# 12ziban.net
KiCad netlist of a schematic drawn in Altium Designer
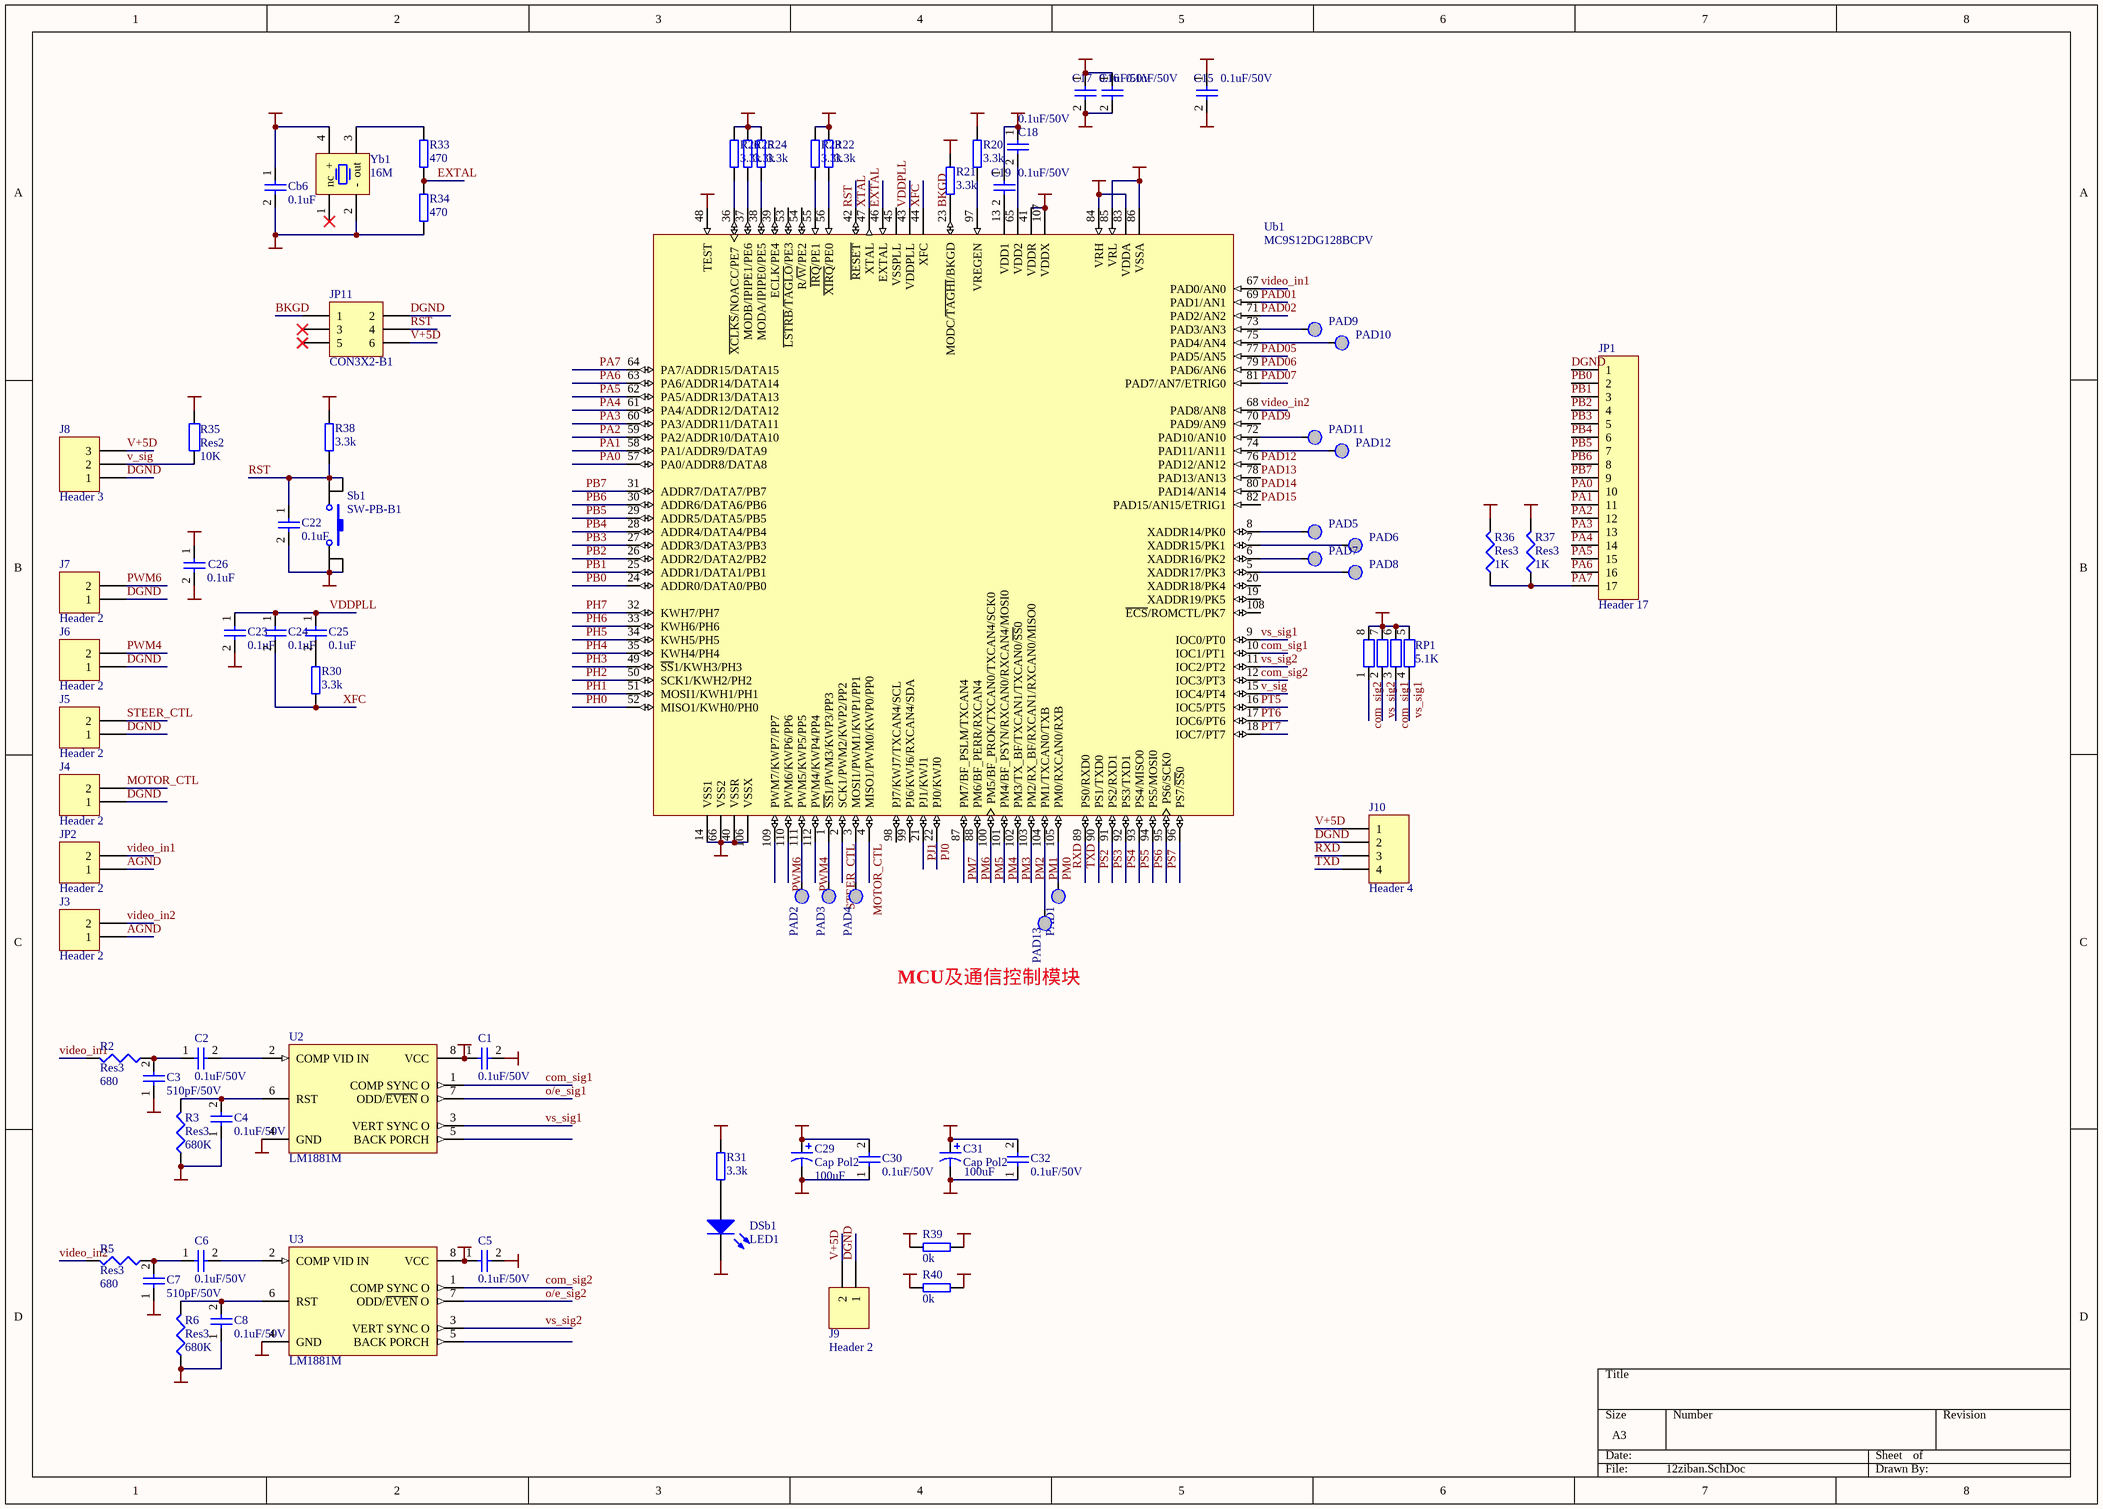
[diagram p0: 12ziban.SchDoc]

(export (version "E")
  (design (tool "Eeschema 10.0.6"))
  (components
    (comp (ref "C1")
      (value "0.1uF/50V")
      (footprint "CR2012-0805")
      (description "Capacitor")
      (fields
        (field (name "MANUFACTURER") "Generic Components")
        (field (name "Comment") "Cap")
        (field (name "PUBLISHER") "Altium Hobart Technology Centre")
      )
      (libsource (lib "YX002") (part "Cap"))
    )
    (comp (ref "C2")
      (value "0.1uF/50V")
      (footprint "CR2012-0805")
      (description "Capacitor")
      (fields
        (field (name "MANUFACTURER") "Generic Components")
        (field (name "Comment") "Cap")
        (field (name "PUBLISHER") "Altium Hobart Technology Centre")
      )
      (libsource (lib "YX002") (part "Cap"))
    )
    (comp (ref "C3")
      (value "510pF/50V")
      (footprint "CR2012-0805")
      (description "Capacitor")
      (fields
        (field (name "MANUFACTURER") "Generic Components")
        (field (name "Comment") "Cap")
        (field (name "PUBLISHER") "Altium Hobart Technology Centre")
      )
      (libsource (lib "YX002") (part "Cap"))
    )
    (comp (ref "C4")
      (value "0.1uF/50V")
      (footprint "CR2012-0805")
      (description "Capacitor")
      (fields
        (field (name "MANUFACTURER") "Generic Components")
        (field (name "Comment") "Cap")
        (field (name "PUBLISHER") "Altium Hobart Technology Centre")
      )
      (libsource (lib "YX002") (part "Cap"))
    )
    (comp (ref "C5")
      (value "0.1uF/50V")
      (footprint "CR2012-0805")
      (description "Capacitor")
      (fields
        (field (name "MANUFACTURER") "Generic Components")
        (field (name "Comment") "Cap")
        (field (name "PUBLISHER") "Altium Hobart Technology Centre")
      )
      (libsource (lib "YX002") (part "Cap"))
    )
    (comp (ref "C6")
      (value "0.1uF/50V")
      (footprint "CR2012-0805")
      (description "Capacitor")
      (fields
        (field (name "MANUFACTURER") "Generic Components")
        (field (name "Comment") "Cap")
        (field (name "PUBLISHER") "Altium Hobart Technology Centre")
      )
      (libsource (lib "YX002") (part "Cap"))
    )
    (comp (ref "C7")
      (value "510pF/50V")
      (footprint "CR2012-0805")
      (description "Capacitor")
      (fields
        (field (name "MANUFACTURER") "Generic Components")
        (field (name "Comment") "Cap")
        (field (name "PUBLISHER") "Altium Hobart Technology Centre")
      )
      (libsource (lib "YX002") (part "Cap"))
    )
    (comp (ref "C8")
      (value "0.1uF/50V")
      (footprint "CR2012-0805")
      (description "Capacitor")
      (fields
        (field (name "MANUFACTURER") "Generic Components")
        (field (name "Comment") "Cap")
        (field (name "PUBLISHER") "Altium Hobart Technology Centre")
      )
      (libsource (lib "YX002") (part "Cap"))
    )
    (comp (ref "C15")
      (value "0.1uF/50V")
      (footprint "CR2012-0805")
      (description "Capacitor")
      (fields
        (field (name "MANUFACTURER") "Generic Components")
        (field (name "Comment") "Cap")
        (field (name "PUBLISHER") "Altium Hobart Technology Centre")
      )
      (libsource (lib "YX002") (part "Cap"))
    )
    (comp (ref "C16")
      (value "0.1uF/50V")
      (footprint "CR2012-0805")
      (description "Capacitor")
      (fields
        (field (name "MANUFACTURER") "Generic Components")
        (field (name "Comment") "Cap")
        (field (name "PUBLISHER") "Altium Hobart Technology Centre")
      )
      (libsource (lib "YX002") (part "Cap"))
    )
    (comp (ref "C17")
      (value "0.1uF/50V")
      (footprint "CR2012-0805")
      (description "Capacitor")
      (fields
        (field (name "MANUFACTURER") "Generic Components")
        (field (name "Comment") "Cap")
        (field (name "PUBLISHER") "Altium Hobart Technology Centre")
      )
      (libsource (lib "YX002") (part "Cap"))
    )
    (comp (ref "C18")
      (value "0.1uF/50V")
      (footprint "CR2012-0805")
      (description "Capacitor")
      (fields
        (field (name "MANUFACTURER") "Generic Components")
        (field (name "Comment") "Cap")
        (field (name "PUBLISHER") "Altium Hobart Technology Centre")
      )
      (libsource (lib "YX002") (part "Cap"))
    )
    (comp (ref "C19")
      (value "0.1uF/50V")
      (footprint "CR2012-0805")
      (description "Capacitor")
      (fields
        (field (name "MANUFACTURER") "Generic Components")
        (field (name "Comment") "Cap")
        (field (name "PUBLISHER") "Altium Hobart Technology Centre")
      )
      (libsource (lib "YX002") (part "Cap"))
    )
    (comp (ref "C22")
      (value "0.1uF")
      (footprint "CR2012-0805")
      (description "Capacitor")
      (fields (field (name "Comment") "Cap") (field (name "PUBLISHER") "Altium Limited"))
      (libsource (lib "BFTC_MD") (part "Cap"))
    )
    (comp (ref "C23")
      (value "0.1uF")
      (footprint "CR2012-0805")
      (description "Capacitor")
      (fields
        (field (name "MANUFACTURER") "Generic Components")
        (field (name "Comment") "Cap")
        (field (name "PUBLISHER") "Altium Hobart Technology Centre")
      )
      (libsource (lib "*") (part "Cap"))
    )
    (comp (ref "C24")
      (value "0.1uF")
      (footprint "CR2012-0805")
      (description "Capacitor")
      (fields
        (field (name "MANUFACTURER") "Generic Components")
        (field (name "Comment") "Cap")
        (field (name "PUBLISHER") "Altium Hobart Technology Centre")
      )
      (libsource (lib "*") (part "Cap"))
    )
    (comp (ref "C25")
      (value "0.1uF")
      (footprint "CR2012-0805")
      (description "Capacitor")
      (fields
        (field (name "MANUFACTURER") "Generic Components")
        (field (name "Comment") "Cap")
        (field (name "PUBLISHER") "Altium Hobart Technology Centre")
      )
      (libsource (lib "*") (part "Cap"))
    )
    (comp (ref "C26")
      (value "0.1uF")
      (footprint "CR2012-0805")
      (description "Capacitor")
      (fields (field (name "Comment") "Cap") (field (name "PUBLISHER") "Altium Limited"))
      (libsource (lib "BFTC_MD") (part "Cap"))
    )
    (comp (ref "C29")
      (value "Cap Pol2")
      (footprint "CR6332-2512")
      (description "Polarized Capacitor (Axial)")
      (fields (field (name "ALTIUM_VALUE") "100uF") (field (name "PUBLISHER") "Altium Limited"))
      (libsource (lib "Miscellaneous Devices") (part "Cap Pol2"))
    )
    (comp (ref "C30")
      (value "0.1uF/50V")
      (footprint "CR2012-0805")
      (description "Capacitor")
      (fields
        (field (name "MANUFACTURER") "Generic Components")
        (field (name "Comment") "Cap")
        (field (name "PUBLISHER") "Altium Hobart Technology Centre")
      )
      (libsource (lib "YX002") (part "Cap"))
    )
    (comp (ref "C31")
      (value "Cap Pol2")
      (footprint "C3216-1206-TA-YX1")
      (description "Polarized Capacitor (Axial)")
      (fields (field (name "ALTIUM_VALUE") "100uF") (field (name "PUBLISHER") "Altium Limited"))
      (libsource (lib "Miscellaneous Devices") (part "Cap Pol2"))
    )
    (comp (ref "C32")
      (value "0.1uF/50V")
      (footprint "CR2012-0805")
      (description "Capacitor")
      (fields
        (field (name "MANUFACTURER") "Generic Components")
        (field (name "Comment") "Cap")
        (field (name "PUBLISHER") "Altium Hobart Technology Centre")
      )
      (libsource (lib "YX002") (part "Cap"))
    )
    (comp (ref "Cb6")
      (value "0.1uF")
      (footprint "CR2012-0805")
      (description "Capacitor")
      (fields
        (field (name "MANUFACTURER") "Generic Components")
        (field (name "Comment") "Cap")
        (field (name "PUBLISHER") "Altium Hobart Technology Centre")
      )
      (libsource (lib "*") (part "Cap"))
    )
    (comp (ref "DSb1")
      (value "LED1")
      (footprint "CR2012-0805")
      (description "Typical RED GaAs LED")
      (fields (field (name "PUBLISHER") "Altium Limited"))
      (libsource (lib "Miscellaneous Devices") (part "LED1"))
    )
    (comp (ref "J3")
      (value "Header 2")
      (footprint "HDR1X2")
      (description "Header, 2-Pin")
      (fields (field (name "PUBLISHER") "Altium Limited"))
      (libsource (lib "Miscellaneous Connectors") (part "Header 2"))
    )
    (comp (ref "J4")
      (value "Header 2")
      (footprint "HDR1X2")
      (description "Header, 2-Pin")
      (fields (field (name "PUBLISHER") "Altium Limited"))
      (libsource (lib "Miscellaneous Connectors") (part "Header 2"))
    )
    (comp (ref "J5")
      (value "Header 2")
      (footprint "HDR1X2")
      (description "Header, 2-Pin")
      (fields (field (name "PUBLISHER") "Altium Limited"))
      (libsource (lib "Miscellaneous Connectors") (part "Header 2"))
    )
    (comp (ref "J6")
      (value "Header 2")
      (footprint "HDR1X2")
      (description "Header, 2-Pin")
      (fields (field (name "PUBLISHER") "Altium Limited"))
      (libsource (lib "Miscellaneous Connectors") (part "Header 2"))
    )
    (comp (ref "J7")
      (value "Header 2")
      (footprint "HDR1X2")
      (description "Header, 2-Pin")
      (fields (field (name "PUBLISHER") "Altium Limited"))
      (libsource (lib "Miscellaneous Connectors") (part "Header 2"))
    )
    (comp (ref "J8")
      (value "Header 3")
      (footprint "HDR1X3")
      (description "Header, 3-Pin")
      (fields (field (name "PUBLISHER") "Altium Limited"))
      (libsource (lib "Miscellaneous Connectors") (part "Header 3"))
    )
    (comp (ref "J9")
      (value "Header 2")
      (footprint "HDR1X2")
      (description "Header, 2-Pin")
      (fields (field (name "PUBLISHER") "Altium Limited"))
      (libsource (lib "") (part "Header 2_1"))
    )
    (comp (ref "J10")
      (value "Header 4")
      (footprint "HDR1X4")
      (description "Header, 4-Pin")
      (fields (field (name "PUBLISHER") "Altium Limited"))
      (libsource (lib "Miscellaneous Connectors") (part "Header 4"))
    )
    (comp (ref "JP1")
      (value "Header 17")
      (footprint "Ts1x17")
      (description "Header, 17-Pin")
      (fields (field (name "PUBLISHER") "Altium Limited"))
      (libsource (lib "Miscellaneous Connectors") (part "Header 17"))
    )
    (comp (ref "JP2")
      (value "Header 2")
      (footprint "HDR1X2")
      (description "Header, 2-Pin")
      (fields (field (name "PUBLISHER") "Altium Limited"))
      (libsource (lib "Miscellaneous Connectors") (part "Header 2"))
    )
    (comp (ref "JP11")
      (value "CON3X2-B1")
      (footprint "HDR2X3")
      (description "Header, 6-Pin, Dual row")
      (fields (field (name "MANUFACTURER") "Generic Components"))
      (libsource (lib "BFTC_MC") (part "CON3X2-B1"))
    )
    (comp (ref "PAD1")
      (value "PAD-YX1")
      (footprint "PAD-TEST-YX1")
      (description "Electrical Bell")
      (fields (field (name "MANUFACTURER") "Generic Components"))
      (libsource (lib "ECU") (part "PAD-YX1"))
    )
    (comp (ref "PAD2")
      (value "PAD-YX1")
      (footprint "PAD-TEST-YX1")
      (description "Electrical Bell")
      (fields (field (name "MANUFACTURER") "Generic Components"))
      (libsource (lib "ECU") (part "PAD-YX1"))
    )
    (comp (ref "PAD3")
      (value "PAD-YX1")
      (footprint "PAD-TEST-YX1")
      (description "Electrical Bell")
      (fields (field (name "MANUFACTURER") "Generic Components"))
      (libsource (lib "ECU") (part "PAD-YX1"))
    )
    (comp (ref "PAD4")
      (value "PAD-YX1")
      (footprint "PAD-TEST-YX1")
      (description "Electrical Bell")
      (fields (field (name "MANUFACTURER") "Generic Components"))
      (libsource (lib "ECU") (part "PAD-YX1"))
    )
    (comp (ref "PAD5")
      (value "PAD-YX1")
      (footprint "PAD-TEST-YX1")
      (description "Electrical Bell")
      (fields (field (name "MANUFACTURER") "Generic Components"))
      (libsource (lib "ECU") (part "PAD-YX1"))
    )
    (comp (ref "PAD6")
      (value "PAD-YX1")
      (footprint "PAD-TEST-YX1")
      (description "Electrical Bell")
      (fields (field (name "MANUFACTURER") "Generic Components"))
      (libsource (lib "ECU") (part "PAD-YX1"))
    )
    (comp (ref "PAD7")
      (value "PAD-YX1")
      (footprint "PAD-TEST-YX1")
      (description "Electrical Bell")
      (fields (field (name "MANUFACTURER") "Generic Components"))
      (libsource (lib "ECU") (part "PAD-YX1"))
    )
    (comp (ref "PAD8")
      (value "PAD-YX1")
      (footprint "PAD-TEST-YX1")
      (description "Electrical Bell")
      (fields (field (name "MANUFACTURER") "Generic Components"))
      (libsource (lib "ECU") (part "PAD-YX1"))
    )
    (comp (ref "PAD9")
      (value "PAD-YX1")
      (footprint "PAD-TEST-YX1")
      (description "Electrical Bell")
      (fields (field (name "MANUFACTURER") "Generic Components"))
      (libsource (lib "ECU") (part "PAD-YX1"))
    )
    (comp (ref "PAD10")
      (value "PAD-YX1")
      (footprint "PAD-TEST-YX1")
      (description "Electrical Bell")
      (fields (field (name "MANUFACTURER") "Generic Components"))
      (libsource (lib "ECU") (part "PAD-YX1"))
    )
    (comp (ref "PAD11")
      (value "PAD-YX1")
      (footprint "PAD-TEST-YX1")
      (description "Electrical Bell")
      (fields (field (name "MANUFACTURER") "Generic Components"))
      (libsource (lib "ECU") (part "PAD-YX1"))
    )
    (comp (ref "PAD12")
      (value "PAD-YX1")
      (footprint "PAD-TEST-YX1")
      (description "Electrical Bell")
      (fields (field (name "MANUFACTURER") "Generic Components"))
      (libsource (lib "ECU") (part "PAD-YX1"))
    )
    (comp (ref "PAD13")
      (value "PAD-YX1")
      (footprint "PAD-TEST-YX1")
      (description "Electrical Bell")
      (fields (field (name "MANUFACTURER") "Generic Components"))
      (libsource (lib "ECU") (part "PAD-YX1"))
    )
    (comp (ref "R2")
      (value "Res3")
      (footprint "CR2012-0805")
      (description "Resistor")
      (fields (field (name "ALTIUM_VALUE") "680") (field (name "PUBLISHER") "Altium Limited"))
      (libsource (lib "Miscellaneous Devices") (part "Res3"))
    )
    (comp (ref "R3")
      (value "Res3")
      (footprint "CR2012-0805")
      (description "Resistor")
      (fields (field (name "ALTIUM_VALUE") "680K") (field (name "PUBLISHER") "Altium Limited"))
      (libsource (lib "Miscellaneous Devices") (part "Res3"))
    )
    (comp (ref "R5")
      (value "Res3")
      (footprint "CR2012-0805")
      (description "Resistor")
      (fields (field (name "ALTIUM_VALUE") "680") (field (name "PUBLISHER") "Altium Limited"))
      (libsource (lib "Miscellaneous Devices") (part "Res3"))
    )
    (comp (ref "R6")
      (value "Res3")
      (footprint "CR2012-0805")
      (description "Resistor")
      (fields (field (name "ALTIUM_VALUE") "680K") (field (name "PUBLISHER") "Altium Limited"))
      (libsource (lib "Miscellaneous Devices") (part "Res3"))
    )
    (comp (ref "R20") (value "3.3k") (footprint "CR2012-0805") (libsource (lib "*") (part "RES2")))
    (comp (ref "R21") (value "3.3k") (footprint "CR2012-0805") (libsource (lib "*") (part "RES2")))
    (comp (ref "R22") (value "3.3k") (footprint "CR2012-0805") (libsource (lib "*") (part "RES2")))
    (comp (ref "R23") (value "3.3k") (footprint "CR2012-0805") (libsource (lib "*") (part "RES2")))
    (comp (ref "R24") (value "3.3k") (footprint "CR2012-0805") (libsource (lib "*") (part "RES2")))
    (comp (ref "R25") (value "3.3k") (footprint "CR2012-0805") (libsource (lib "*") (part "RES2")))
    (comp (ref "R26") (value "3.3k") (footprint "CR2012-0805") (libsource (lib "*") (part "RES2")))
    (comp (ref "R30") (value "3.3k") (footprint "CR2012-0805") (libsource (lib "*") (part "RES2")))
    (comp (ref "R31") (value "3.3k") (footprint "CR2012-0805") (libsource (lib "*") (part "RES2")))
    (comp (ref "R33") (value "470") (footprint "CR2012-0805") (libsource (lib "*") (part "RES2")))
    (comp (ref "R34") (value "470") (footprint "CR2012-0805") (libsource (lib "*") (part "RES2")))
    (comp (ref "R35")
      (value "Res2")
      (footprint "CR2012-0805")
      (description "Resistor")
      (fields (field (name "ALTIUM_VALUE") "10K") (field (name "PUBLISHER") "Altium Limited"))
      (libsource (lib "Miscellaneous Devices") (part "Res2"))
    )
    (comp (ref "R36")
      (value "Res3")
      (footprint "CR2012-0805")
      (description "Resistor")
      (fields (field (name "ALTIUM_VALUE") "1K") (field (name "PUBLISHER") "Altium Limited"))
      (libsource (lib "Miscellaneous Devices") (part "Res3"))
    )
    (comp (ref "R37")
      (value "Res3")
      (footprint "CR2012-0805")
      (description "Resistor")
      (fields (field (name "ALTIUM_VALUE") "1K") (field (name "PUBLISHER") "Altium Limited"))
      (libsource (lib "Miscellaneous Devices") (part "Res3"))
    )
    (comp (ref "R38") (value "3.3k") (footprint "CR2012-0805") (libsource (lib "*") (part "RES2")))
    (comp (ref "R39") (value "0k") (footprint "CR2012-0805") (libsource (lib "*") (part "RES2")))
    (comp (ref "R40") (value "0k") (footprint "CR2012-0805") (libsource (lib "*") (part "RES2")))
    (comp (ref "RP1")
      (value "5.1K")
      (footprint "RP4_YX1")
      (description "Resistor")
      (fields
        (field (name "MANUFACTURER") "Generic Components")
        (field (name "Comment") "RESP4_YX1")
        (field (name "PUBLISHER") "Altium Hobart Technology Centre")
      )
      (libsource (lib "YX002") (part "RESP4_YX1"))
    )
    (comp (ref "Sb1")
      (value "SW-PB-B1")
      (footprint "SW2-4-B1")
      (description "Switch")
      (fields (field (name "MANUFACTURER") "Generic Components"))
      (libsource (lib "BFTC_MD") (part "SW-PB-B1"))
    )
    (comp (ref "U2")
      (value "LM1881M")
      (footprint "SO-8")
      (description "Video Sync Separator")
      (fields (field (name "PUBLISHER") "Altium Limited"))
      (libsource (lib "NSC Video Sync Circuit") (part "LM1881M"))
    )
    (comp (ref "U3")
      (value "LM1881M")
      (footprint "SO-8")
      (description "Video Sync Separator")
      (fields (field (name "PUBLISHER") "Altium Limited"))
      (libsource (lib "NSC Video Sync Circuit") (part "LM1881M"))
    )
    (comp (ref "Ub1")
      (value "MC9S12DG128BCPV")
      (footprint "987-01")
      (description "16-Bit Microcontroller")
      (fields (field (name "PUBLISHER") "Altium Limited"))
      (libsource (lib "Motorola Microcontroller 16-Bit") (part "MC9S12DG128BCPV"))
    )
    (comp (ref "Yb1")
      (value "16M")
      (footprint "XYT")
      (description "Crystal Oscillator")
      (fields
        (field (name "MANUFACTURER") "Generic Components")
        (field (name "Comment") "XTAL")
        (field (name "PUBLISHER") "Altium Hobart Technology Centre")
      )
      (libsource (lib "*") (part "XTAL-YX2"))
    )
  )
  (nets
    (net (code "1") (name "/BKGD") (class "Default")
      (node (ref "JP11") (pin "1") (pinfunction "1_1") (pintype "passive"))
      (node (ref "R21") (pin "2") (pinfunction "2_2") (pintype "passive"))
      (node (ref "Ub1") (pin "23") (pinfunction "MODC/~{TAGHI}/BKGD_23") (pintype "bidirectional"))
    )
    (net (code "2") (name "/EXTAL") (class "Default")
      (node (ref "R33") (pin "2") (pinfunction "2_2") (pintype "passive"))
      (node (ref "R34") (pin "1") (pinfunction "1_1") (pintype "passive"))
      (node (ref "Ub1") (pin "46") (pinfunction "EXTAL_46") (pintype "input"))
    )
    (net (code "3") (name "/MOTOR_CTL") (class "Default")
      (node (ref "J4") (pin "2") (pinfunction "2_2") (pintype "passive"))
      (node (ref "Ub1") (pin "4") (pinfunction "MISO1/PWM0/KWP0/PP0_4") (pintype "bidirectional"))
    )
    (net (code "4") (name "/PA0") (class "Default")
      (node (ref "JP1") (pin "10") (pinfunction "10_10") (pintype "passive"))
      (node (ref "Ub1") (pin "57") (pinfunction "PA0/ADDR8/DATA8_57") (pintype "bidirectional"))
    )
    (net (code "5") (name "/PA1") (class "Default")
      (node (ref "JP1") (pin "11") (pinfunction "11_11") (pintype "passive"))
      (node (ref "Ub1") (pin "58") (pinfunction "PA1/ADDR9/DATA9_58") (pintype "bidirectional"))
    )
    (net (code "6") (name "/PA2") (class "Default")
      (node (ref "JP1") (pin "12") (pinfunction "12_12") (pintype "passive"))
      (node (ref "Ub1") (pin "59") (pinfunction "PA2/ADDR10/DATA10_59") (pintype "bidirectional"))
    )
    (net (code "7") (name "/PA3") (class "Default")
      (node (ref "JP1") (pin "13") (pinfunction "13_13") (pintype "passive"))
      (node (ref "Ub1") (pin "60") (pinfunction "PA3/ADDR11/DATA11_60") (pintype "bidirectional"))
    )
    (net (code "8") (name "/PA4") (class "Default")
      (node (ref "JP1") (pin "14") (pinfunction "14_14") (pintype "passive"))
      (node (ref "Ub1") (pin "61") (pinfunction "PA4/ADDR12/DATA12_61") (pintype "bidirectional"))
    )
    (net (code "9") (name "/PA5") (class "Default")
      (node (ref "JP1") (pin "15") (pinfunction "15_15") (pintype "passive"))
      (node (ref "Ub1") (pin "62") (pinfunction "PA5/ADDR13/DATA13_62") (pintype "bidirectional"))
    )
    (net (code "10") (name "/PA6") (class "Default")
      (node (ref "JP1") (pin "16") (pinfunction "16_16") (pintype "passive"))
      (node (ref "Ub1") (pin "63") (pinfunction "PA6/ADDR14/DATA14_63") (pintype "bidirectional"))
    )
    (net (code "11") (name "/PA7") (class "Default")
      (node (ref "JP1") (pin "17") (pinfunction "17_17") (pintype "passive"))
      (node (ref "R36") (pin "1") (pinfunction "1_1") (pintype "passive"))
      (node (ref "R37") (pin "1") (pinfunction "1_1") (pintype "passive"))
      (node (ref "Ub1") (pin "64") (pinfunction "PA7/ADDR15/DATA15_64") (pintype "bidirectional"))
    )
    (net (code "12") (name "/PAD01") (class "Default")
      (node (ref "Ub1") (pin "69") (pinfunction "PAD1/AN1_69") (pintype "input"))
    )
    (net (code "13") (name "/PAD02") (class "Default")
      (node (ref "Ub1") (pin "71") (pinfunction "PAD2/AN2_71") (pintype "input"))
    )
    (net (code "14") (name "/PAD05") (class "Default")
      (node (ref "Ub1") (pin "77") (pinfunction "PAD5/AN5_77") (pintype "input"))
    )
    (net (code "15") (name "/PAD06") (class "Default")
      (node (ref "Ub1") (pin "79") (pinfunction "PAD6/AN6_79") (pintype "input"))
    )
    (net (code "16") (name "/PAD07") (class "Default")
      (node (ref "Ub1") (pin "81") (pinfunction "PAD7/AN7/ETRIG0_81") (pintype "input"))
    )
    (net (code "17") (name "/PAD9") (class "Default")
      (node (ref "Ub1") (pin "70") (pinfunction "PAD9/AN9_70") (pintype "input"))
    )
    (net (code "18") (name "/PAD12") (class "Default")
      (node (ref "Ub1") (pin "76") (pinfunction "PAD12/AN12_76") (pintype "input"))
    )
    (net (code "19") (name "/PAD13") (class "Default")
      (node (ref "Ub1") (pin "78") (pinfunction "PAD13/AN13_78") (pintype "input"))
    )
    (net (code "20") (name "/PAD14") (class "Default")
      (node (ref "Ub1") (pin "80") (pinfunction "PAD14/AN14_80") (pintype "input"))
    )
    (net (code "21") (name "/PAD15") (class "Default")
      (node (ref "Ub1") (pin "82") (pinfunction "PAD15/AN15/ETRIG1_82") (pintype "input"))
    )
    (net (code "22") (name "/PB0") (class "Default")
      (node (ref "JP1") (pin "2") (pinfunction "2_2") (pintype "passive"))
      (node (ref "Ub1") (pin "24") (pinfunction "ADDR0/DATA0/PB0_24") (pintype "bidirectional"))
    )
    (net (code "23") (name "/PB1") (class "Default")
      (node (ref "JP1") (pin "3") (pinfunction "3_3") (pintype "passive"))
      (node (ref "Ub1") (pin "25") (pinfunction "ADDR1/DATA1/PB1_25") (pintype "bidirectional"))
    )
    (net (code "24") (name "/PB2") (class "Default")
      (node (ref "JP1") (pin "4") (pinfunction "4_4") (pintype "passive"))
      (node (ref "Ub1") (pin "26") (pinfunction "ADDR2/DATA2/PB2_26") (pintype "bidirectional"))
    )
    (net (code "25") (name "/PB3") (class "Default")
      (node (ref "JP1") (pin "5") (pinfunction "5_5") (pintype "passive"))
      (node (ref "Ub1") (pin "27") (pinfunction "ADDR3/DATA3/PB3_27") (pintype "bidirectional"))
    )
    (net (code "26") (name "/PB4") (class "Default")
      (node (ref "JP1") (pin "6") (pinfunction "6_6") (pintype "passive"))
      (node (ref "Ub1") (pin "28") (pinfunction "ADDR4/DATA4/PB4_28") (pintype "bidirectional"))
    )
    (net (code "27") (name "/PB5") (class "Default")
      (node (ref "JP1") (pin "7") (pinfunction "7_7") (pintype "passive"))
      (node (ref "Ub1") (pin "29") (pinfunction "ADDR5/DATA5/PB5_29") (pintype "bidirectional"))
    )
    (net (code "28") (name "/PB6") (class "Default")
      (node (ref "JP1") (pin "8") (pinfunction "8_8") (pintype "passive"))
      (node (ref "Ub1") (pin "30") (pinfunction "ADDR6/DATA6/PB6_30") (pintype "bidirectional"))
    )
    (net (code "29") (name "/PB7") (class "Default")
      (node (ref "JP1") (pin "9") (pinfunction "9_9") (pintype "passive"))
      (node (ref "Ub1") (pin "31") (pinfunction "ADDR7/DATA7/PB7_31") (pintype "bidirectional"))
    )
    (net (code "30") (name "/PH0") (class "Default")
      (node (ref "Ub1") (pin "52") (pinfunction "MISO1/KWH0/PH0_52") (pintype "bidirectional"))
    )
    (net (code "31") (name "/PH1") (class "Default")
      (node (ref "Ub1") (pin "51") (pinfunction "MOSI1/KWH1/PH1_51") (pintype "bidirectional"))
    )
    (net (code "32") (name "/PH2") (class "Default")
      (node (ref "Ub1") (pin "50") (pinfunction "SCK1/KWH2/PH2_50") (pintype "bidirectional"))
    )
    (net (code "33") (name "/PH3") (class "Default")
      (node (ref "Ub1") (pin "49") (pinfunction "~{SS}1/KWH3/PH3_49") (pintype "bidirectional"))
    )
    (net (code "34") (name "/PH4") (class "Default")
      (node (ref "Ub1") (pin "35") (pinfunction "KWH4/PH4_35") (pintype "bidirectional"))
    )
    (net (code "35") (name "/PH5") (class "Default")
      (node (ref "Ub1") (pin "34") (pinfunction "KWH5/PH5_34") (pintype "bidirectional"))
    )
    (net (code "36") (name "/PH6") (class "Default")
      (node (ref "Ub1") (pin "33") (pinfunction "KWH6/PH6_33") (pintype "bidirectional"))
    )
    (net (code "37") (name "/PH7") (class "Default")
      (node (ref "Ub1") (pin "32") (pinfunction "KWH7/PH7_32") (pintype "bidirectional"))
    )
    (net (code "38") (name "/PJ0") (class "Default")
      (node (ref "Ub1") (pin "22") (pinfunction "PJ0/KWJ0_22") (pintype "bidirectional"))
    )
    (net (code "39") (name "/PJ1") (class "Default")
      (node (ref "Ub1") (pin "21") (pinfunction "PJ1/KWJ1_21") (pintype "bidirectional"))
    )
    (net (code "40") (name "/PM0") (class "Default")
      (node (ref "PAD1") (pin "1") (pinfunction "A_1") (pintype "passive"))
      (node (ref "Ub1") (pin "105") (pinfunction "PM0/RXCAN0/RXB_105") (pintype "bidirectional"))
    )
    (net (code "41") (name "/PM1") (class "Default")
      (node (ref "PAD13") (pin "1") (pinfunction "A_1") (pintype "passive"))
      (node (ref "Ub1") (pin "104") (pinfunction "PM1/TXCAN0/TXB_104") (pintype "bidirectional"))
    )
    (net (code "42") (name "/PM2") (class "Default")
      (node (ref "Ub1") (pin "103") (pinfunction "PM2/RX_BF/RXCAN1/RXCAN0/MISO0_103") (pintype "bidirectional"))
    )
    (net (code "43") (name "/PM3") (class "Default")
      (node (ref "Ub1") (pin "102") (pinfunction "PM3/TX_BF/TXCAN1/TXCAN0/~{SS}0_102") (pintype "bidirectional"))
    )
    (net (code "44") (name "/PM4") (class "Default")
      (node (ref "Ub1") (pin "101") (pinfunction "PM4/BF_PSYN/RXCAN0/RXCAN4/MOSI0_101") (pintype "bidirectional"))
    )
    (net (code "45") (name "/PM5") (class "Default")
      (node (ref "Ub1") (pin "100") (pinfunction "PM5/BF_PROK/TXCAN0/TXCAN4/SCK0_100") (pintype "bidirectional"))
    )
    (net (code "46") (name "/PM6") (class "Default")
      (node (ref "Ub1") (pin "88") (pinfunction "PM6/BF_PERR/RXCAN4_88") (pintype "bidirectional"))
    )
    (net (code "47") (name "/PM7") (class "Default")
      (node (ref "Ub1") (pin "87") (pinfunction "PM7/BF_PSLM/TXCAN4_87") (pintype "bidirectional"))
    )
    (net (code "48") (name "/PS2") (class "Default")
      (node (ref "Ub1") (pin "91") (pinfunction "PS2/RXD1_91") (pintype "bidirectional"))
    )
    (net (code "49") (name "/PS3") (class "Default")
      (node (ref "Ub1") (pin "92") (pinfunction "PS3/TXD1_92") (pintype "bidirectional"))
    )
    (net (code "50") (name "/PS4") (class "Default")
      (node (ref "Ub1") (pin "93") (pinfunction "PS4/MISO0_93") (pintype "bidirectional"))
    )
    (net (code "51") (name "/PS5") (class "Default")
      (node (ref "Ub1") (pin "94") (pinfunction "PS5/MOSI0_94") (pintype "bidirectional"))
    )
    (net (code "52") (name "/PS6") (class "Default")
      (node (ref "Ub1") (pin "95") (pinfunction "PS6/SCK0_95") (pintype "bidirectional"))
    )
    (net (code "53") (name "/PS7") (class "Default")
      (node (ref "Ub1") (pin "96") (pinfunction "PS7/~{SS}0_96") (pintype "bidirectional"))
    )
    (net (code "54") (name "/PT5") (class "Default")
      (node (ref "Ub1") (pin "16") (pinfunction "IOC5/PT5_16") (pintype "bidirectional"))
    )
    (net (code "55") (name "/PT6") (class "Default")
      (node (ref "Ub1") (pin "17") (pinfunction "IOC6/PT6_17") (pintype "bidirectional"))
    )
    (net (code "56") (name "/PT7") (class "Default")
      (node (ref "Ub1") (pin "18") (pinfunction "IOC7/PT7_18") (pintype "bidirectional"))
    )
    (net (code "57") (name "/PWM4") (class "Default")
      (node (ref "J6") (pin "2") (pinfunction "2_2") (pintype "passive"))
      (node (ref "Ub1") (pin "112") (pinfunction "PWM4/KWP4/PP4_112") (pintype "bidirectional"))
    )
    (net (code "58") (name "/PWM6") (class "Default")
      (node (ref "J7") (pin "2") (pinfunction "2_2") (pintype "passive"))
      (node (ref "Ub1") (pin "110") (pinfunction "PWM6/KWP6/PP6_110") (pintype "bidirectional"))
    )
    (net (code "59") (name "/RST") (class "Default")
      (node (ref "C22") (pin "1") (pinfunction "1_1") (pintype "passive"))
      (node (ref "JP11") (pin "4") (pinfunction "4_4") (pintype "passive"))
      (node (ref "R38") (pin "1") (pinfunction "1_1") (pintype "passive"))
      (node (ref "Sb1") (pin "1") (pinfunction "1_1") (pintype "passive"))
      (node (ref "Sb1") (pin "4") (pinfunction "4_4") (pintype "passive"))
      (node (ref "Ub1") (pin "42") (pinfunction "~{RESET}_42") (pintype "bidirectional"))
    )
    (net (code "60") (name "/RXD") (class "Default")
      (node (ref "J10") (pin "3") (pinfunction "3_3") (pintype "passive"))
      (node (ref "Ub1") (pin "89") (pinfunction "PS0/RXD0_89") (pintype "bidirectional"))
    )
    (net (code "61") (name "/STEER_CTL") (class "Default")
      (node (ref "J5") (pin "2") (pinfunction "2_2") (pintype "passive"))
      (node (ref "Ub1") (pin "2") (pinfunction "SCK1/PWM2/KWP2/PP2_2") (pintype "bidirectional"))
    )
    (net (code "62") (name "/TXD") (class "Default")
      (node (ref "J10") (pin "4") (pinfunction "4_4") (pintype "passive"))
      (node (ref "Ub1") (pin "90") (pinfunction "PS1/TXD0_90") (pintype "bidirectional"))
    )
    (net (code "63") (name "/VDDPLL") (class "Default")
      (node (ref "C23") (pin "1") (pinfunction "1_1") (pintype "passive"))
      (node (ref "C24") (pin "1") (pinfunction "1_1") (pintype "passive"))
      (node (ref "C25") (pin "1") (pinfunction "1_1") (pintype "passive"))
      (node (ref "Ub1") (pin "43") (pinfunction "VDDPLL_43") (pintype "power_in"))
    )
    (net (code "64") (name "/XFC") (class "Default")
      (node (ref "C24") (pin "2") (pinfunction "2_2") (pintype "passive"))
      (node (ref "R30") (pin "1") (pinfunction "1_1") (pintype "passive"))
      (node (ref "Ub1") (pin "44") (pinfunction "XFC_44") (pintype "passive"))
    )
    (net (code "65") (name "/XTAL") (class "Default")
      (node (ref "Ub1") (pin "47") (pinfunction "XTAL_47") (pintype "output"))
    )
    (net (code "66") (name "/com_sig1") (class "Default")
      (node (ref "RP1") (pin "3") (pinfunction "3_3") (pintype "passive"))
      (node (ref "U2") (pin "1") (pinfunction "COMP_SYNC_O_1") (pintype "output"))
      (node (ref "Ub1") (pin "10") (pinfunction "IOC1/PT1_10") (pintype "bidirectional"))
    )
    (net (code "67") (name "/com_sig2") (class "Default")
      (node (ref "RP1") (pin "1") (pinfunction "1_1") (pintype "passive"))
      (node (ref "U3") (pin "1") (pinfunction "COMP_SYNC_O_1") (pintype "output"))
      (node (ref "Ub1") (pin "12") (pinfunction "IOC3/PT3_12") (pintype "bidirectional"))
    )
    (net (code "68") (name "/o{slash}e_sig1") (class "Default")
      (node (ref "U2") (pin "7") (pinfunction "ODD/~{EVEN}_O_7") (pintype "output"))
    )
    (net (code "69") (name "/o{slash}e_sig2") (class "Default")
      (node (ref "U3") (pin "7") (pinfunction "ODD/~{EVEN}_O_7") (pintype "output"))
    )
    (net (code "70") (name "/v_sig") (class "Default")
      (node (ref "J8") (pin "2") (pinfunction "2_2") (pintype "passive"))
      (node (ref "R35") (pin "1") (pinfunction "1_1") (pintype "passive"))
      (node (ref "Ub1") (pin "15") (pinfunction "IOC4/PT4_15") (pintype "bidirectional"))
    )
    (net (code "71") (name "/video_in1") (class "Default")
      (node (ref "JP2") (pin "2") (pinfunction "2_2") (pintype "passive"))
      (node (ref "R2") (pin "2") (pinfunction "2_2") (pintype "passive"))
      (node (ref "Ub1") (pin "67") (pinfunction "PAD0/AN0_67") (pintype "input"))
    )
    (net (code "72") (name "/video_in2") (class "Default")
      (node (ref "J3") (pin "2") (pinfunction "2_2") (pintype "passive"))
      (node (ref "R5") (pin "2") (pinfunction "2_2") (pintype "passive"))
      (node (ref "Ub1") (pin "68") (pinfunction "PAD8/AN8_68") (pintype "input"))
    )
    (net (code "73") (name "/vs_sig1") (class "Default")
      (node (ref "RP1") (pin "4") (pinfunction "4_4") (pintype "passive"))
      (node (ref "U2") (pin "3") (pinfunction "VERT_SYNC_O_3") (pintype "output"))
      (node (ref "Ub1") (pin "9") (pinfunction "IOC0/PT0_9") (pintype "bidirectional"))
    )
    (net (code "74") (name "/vs_sig2") (class "Default")
      (node (ref "RP1") (pin "2") (pinfunction "2_2") (pintype "passive"))
      (node (ref "U3") (pin "3") (pinfunction "VERT_SYNC_O_3") (pintype "output"))
      (node (ref "Ub1") (pin "11") (pinfunction "IOC2/PT2_11") (pintype "bidirectional"))
    )
    (net (code "75") (name "AGND") (class "Default")
      (node (ref "C1") (pin "2") (pinfunction "2_2") (pintype "passive"))
      (node (ref "C15") (pin "2") (pinfunction "2_2") (pintype "passive"))
      (node (ref "C3") (pin "1") (pinfunction "1_1") (pintype "passive"))
      (node (ref "C31") (pin "2") (pinfunction "2_2") (pintype "passive"))
      (node (ref "C32") (pin "1") (pinfunction "1_1") (pintype "passive"))
      (node (ref "C4") (pin "1") (pinfunction "1_1") (pintype "passive"))
      (node (ref "C5") (pin "2") (pinfunction "2_2") (pintype "passive"))
      (node (ref "C7") (pin "1") (pinfunction "1_1") (pintype "passive"))
      (node (ref "C8") (pin "1") (pinfunction "1_1") (pintype "passive"))
      (node (ref "J3") (pin "1") (pinfunction "1_1") (pintype "passive"))
      (node (ref "JP2") (pin "1") (pinfunction "1_1") (pintype "passive"))
      (node (ref "R3") (pin "1") (pinfunction "1_1") (pintype "passive"))
      (node (ref "R40") (pin "1") (pinfunction "1_1") (pintype "passive"))
      (node (ref "R6") (pin "1") (pinfunction "1_1") (pintype "passive"))
      (node (ref "U2") (pin "4") (pinfunction "GND_4") (pintype "power_in"))
      (node (ref "U3") (pin "4") (pinfunction "GND_4") (pintype "power_in"))
      (node (ref "Ub1") (pin "85") (pinfunction "VRL_85") (pintype "input"))
      (node (ref "Ub1") (pin "86") (pinfunction "VSSA_86") (pintype "power_in"))
    )
    (net (code "76") (name "DGND") (class "Default")
      (node (ref "C16") (pin "2") (pinfunction "2_2") (pintype "passive"))
      (node (ref "C17") (pin "2") (pinfunction "2_2") (pintype "passive"))
      (node (ref "C18") (pin "1") (pinfunction "1_1") (pintype "passive"))
      (node (ref "C19") (pin "1") (pinfunction "1_1") (pintype "passive"))
      (node (ref "C22") (pin "2") (pinfunction "2_2") (pintype "passive"))
      (node (ref "C23") (pin "2") (pinfunction "2_2") (pintype "passive"))
      (node (ref "C26") (pin "2") (pinfunction "2_2") (pintype "passive"))
      (node (ref "C29") (pin "2") (pinfunction "2_2") (pintype "passive"))
      (node (ref "C30") (pin "1") (pinfunction "1_1") (pintype "passive"))
      (node (ref "Cb6") (pin "2") (pinfunction "2_2") (pintype "passive"))
      (node (ref "DSb1") (pin "2") (pinfunction "K_2") (pintype "passive"))
      (node (ref "J10") (pin "2") (pinfunction "2_2") (pintype "passive"))
      (node (ref "J4") (pin "1") (pinfunction "1_1") (pintype "passive"))
      (node (ref "J5") (pin "1") (pinfunction "1_1") (pintype "passive"))
      (node (ref "J6") (pin "1") (pinfunction "1_1") (pintype "passive"))
      (node (ref "J7") (pin "1") (pinfunction "1_1") (pintype "passive"))
      (node (ref "J8") (pin "1") (pinfunction "1_1") (pintype "passive"))
      (node (ref "J9") (pin "1") (pinfunction "1_1") (pintype "passive"))
      (node (ref "JP1") (pin "1") (pinfunction "1_1") (pintype "passive"))
      (node (ref "JP11") (pin "2") (pinfunction "2_2") (pintype "passive"))
      (node (ref "R24") (pin "1") (pinfunction "1_1") (pintype "passive"))
      (node (ref "R25") (pin "1") (pinfunction "1_1") (pintype "passive"))
      (node (ref "R26") (pin "1") (pinfunction "1_1") (pintype "passive"))
      (node (ref "R34") (pin "2") (pinfunction "2_2") (pintype "passive"))
      (node (ref "R37") (pin "2") (pinfunction "2_2") (pintype "passive"))
      (node (ref "R40") (pin "2") (pinfunction "2_2") (pintype "passive"))
      (node (ref "Sb1") (pin "2") (pinfunction "2_2") (pintype "passive"))
      (node (ref "Sb1") (pin "3") (pinfunction "3_3") (pintype "passive"))
      (node (ref "Ub1") (pin "106") (pinfunction "VSSX_106") (pintype "power_in"))
      (node (ref "Ub1") (pin "14") (pinfunction "VSS1_14") (pintype "power_in"))
      (node (ref "Ub1") (pin "40") (pinfunction "VSSR_40") (pintype "power_in"))
      (node (ref "Ub1") (pin "48") (pinfunction "TEST_48") (pintype "input"))
      (node (ref "Ub1") (pin "66") (pinfunction "VSS2_66") (pintype "power_in"))
      (node (ref "Yb1") (pin "2") (pinfunction "-_2") (pintype "passive"))
    )
    (net (code "77") (name "Net-(C2-Pad1)") (class "Default")
      (node (ref "C2") (pin "1") (pinfunction "1_1") (pintype "passive"))
      (node (ref "C3") (pin "2") (pinfunction "2_2") (pintype "passive"))
      (node (ref "R2") (pin "1") (pinfunction "1_1") (pintype "passive"))
    )
    (net (code "78") (name "Net-(C6-Pad1)") (class "Default")
      (node (ref "C6") (pin "1") (pinfunction "1_1") (pintype "passive"))
      (node (ref "C7") (pin "2") (pinfunction "2_2") (pintype "passive"))
      (node (ref "R5") (pin "1") (pinfunction "1_1") (pintype "passive"))
    )
    (net (code "79") (name "Net-(C25-Pad2)") (class "Default")
      (node (ref "C25") (pin "2") (pinfunction "2_2") (pintype "passive"))
      (node (ref "R30") (pin "2") (pinfunction "2_2") (pintype "passive"))
    )
    (net (code "80") (name "Net-(DSb1-A)") (class "Default")
      (node (ref "DSb1") (pin "1") (pinfunction "A_1") (pintype "passive"))
      (node (ref "R31") (pin "1") (pinfunction "1_1") (pintype "passive"))
    )
    (net (code "81") (name "Net-(PAD2-A)") (class "Default")
      (node (ref "PAD2") (pin "1") (pinfunction "A_1") (pintype "passive"))
      (node (ref "Ub1") (pin "111") (pinfunction "PWM5/KWP5/PP5_111") (pintype "bidirectional"))
    )
    (net (code "82") (name "Net-(PAD3-A)") (class "Default")
      (node (ref "PAD3") (pin "1") (pinfunction "A_1") (pintype "passive"))
      (node (ref "Ub1") (pin "1") (pinfunction "~{SS}1/PWM3/KWP3/PP3_1") (pintype "bidirectional"))
    )
    (net (code "83") (name "Net-(PAD4-A)") (class "Default")
      (node (ref "PAD4") (pin "1") (pinfunction "A_1") (pintype "passive"))
      (node (ref "Ub1") (pin "3") (pinfunction "MOSI1/PWM1/KWP1/PP1_3") (pintype "bidirectional"))
    )
    (net (code "84") (name "Net-(PAD5-A)") (class "Default")
      (node (ref "PAD5") (pin "1") (pinfunction "A_1") (pintype "passive"))
      (node (ref "Ub1") (pin "8") (pinfunction "XADDR14/PK0_8") (pintype "bidirectional"))
    )
    (net (code "85") (name "Net-(PAD6-A)") (class "Default")
      (node (ref "PAD6") (pin "1") (pinfunction "A_1") (pintype "passive"))
      (node (ref "Ub1") (pin "7") (pinfunction "XADDR15/PK1_7") (pintype "bidirectional"))
    )
    (net (code "86") (name "Net-(PAD7-A)") (class "Default")
      (node (ref "PAD7") (pin "1") (pinfunction "A_1") (pintype "passive"))
      (node (ref "Ub1") (pin "6") (pinfunction "XADDR16/PK2_6") (pintype "bidirectional"))
    )
    (net (code "87") (name "Net-(PAD8-A)") (class "Default")
      (node (ref "PAD8") (pin "1") (pinfunction "A_1") (pintype "passive"))
      (node (ref "Ub1") (pin "5") (pinfunction "XADDR17/PK3_5") (pintype "bidirectional"))
    )
    (net (code "88") (name "Net-(PAD9-A)") (class "Default")
      (node (ref "PAD9") (pin "1") (pinfunction "A_1") (pintype "passive"))
      (node (ref "Ub1") (pin "73") (pinfunction "PAD3/AN3_73") (pintype "input"))
    )
    (net (code "89") (name "Net-(PAD10-A)") (class "Default")
      (node (ref "PAD10") (pin "1") (pinfunction "A_1") (pintype "passive"))
      (node (ref "Ub1") (pin "75") (pinfunction "PAD4/AN4_75") (pintype "input"))
    )
    (net (code "90") (name "Net-(PAD11-A)") (class "Default")
      (node (ref "PAD11") (pin "1") (pinfunction "A_1") (pintype "passive"))
      (node (ref "Ub1") (pin "72") (pinfunction "PAD10/AN10_72") (pintype "input"))
    )
    (net (code "91") (name "Net-(PAD12-A)") (class "Default")
      (node (ref "PAD12") (pin "1") (pinfunction "A_1") (pintype "passive"))
      (node (ref "Ub1") (pin "74") (pinfunction "PAD11/AN11_74") (pintype "input"))
    )
    (net (code "92") (name "Net-(U2-COMP_VID_IN)") (class "Default")
      (node (ref "C2") (pin "2") (pinfunction "2_2") (pintype "passive"))
      (node (ref "U2") (pin "2") (pinfunction "COMP_VID_IN_2") (pintype "input"))
    )
    (net (code "93") (name "Net-(U2-RST)") (class "Default")
      (node (ref "C4") (pin "2") (pinfunction "2_2") (pintype "passive"))
      (node (ref "R3") (pin "2") (pinfunction "2_2") (pintype "passive"))
      (node (ref "U2") (pin "6") (pinfunction "RST_6") (pintype "passive"))
    )
    (net (code "94") (name "Net-(U3-COMP_VID_IN)") (class "Default")
      (node (ref "C6") (pin "2") (pinfunction "2_2") (pintype "passive"))
      (node (ref "U3") (pin "2") (pinfunction "COMP_VID_IN_2") (pintype "input"))
    )
    (net (code "95") (name "Net-(U3-RST)") (class "Default")
      (node (ref "C8") (pin "2") (pinfunction "2_2") (pintype "passive"))
      (node (ref "R6") (pin "2") (pinfunction "2_2") (pintype "passive"))
      (node (ref "U3") (pin "6") (pinfunction "RST_6") (pintype "passive"))
    )
    (net (code "96") (name "Net-(Ub1-MODA{slash}IPIPE0{slash}PE5)") (class "Default")
      (node (ref "R24") (pin "2") (pinfunction "2_2") (pintype "passive"))
      (node (ref "Ub1") (pin "38") (pinfunction "MODA/IPIPE0/PE5_38") (pintype "bidirectional"))
    )
    (net (code "97") (name "Net-(Ub1-MODB{slash}IPIPE1{slash}PE6)") (class "Default")
      (node (ref "R25") (pin "2") (pinfunction "2_2") (pintype "passive"))
      (node (ref "Ub1") (pin "37") (pinfunction "MODB/IPIPE1/PE6_37") (pintype "bidirectional"))
    )
    (net (code "98") (name "Net-(Ub1-VDD1)") (class "Default")
      (node (ref "C19") (pin "2") (pinfunction "2_2") (pintype "passive"))
      (node (ref "Ub1") (pin "13") (pinfunction "VDD1_13") (pintype "power_in"))
    )
    (net (code "99") (name "Net-(Ub1-VDD2)") (class "Default")
      (node (ref "C18") (pin "2") (pinfunction "2_2") (pintype "passive"))
      (node (ref "Ub1") (pin "65") (pinfunction "VDD2_65") (pintype "power_in"))
    )
    (net (code "100") (name "Net-(Ub1-VREGEN)") (class "Default")
      (node (ref "R20") (pin "2") (pinfunction "2_2") (pintype "passive"))
      (node (ref "Ub1") (pin "97") (pinfunction "VREGEN_97") (pintype "input"))
    )
    (net (code "101") (name "Net-(Ub1-~{IRQ}{slash}PE1)") (class "Default")
      (node (ref "R23") (pin "2") (pinfunction "2_2") (pintype "passive"))
      (node (ref "Ub1") (pin "55") (pinfunction "~{IRQ}/PE1_55") (pintype "input"))
    )
    (net (code "102") (name "Net-(Ub1-~{XCLKS}{slash}NOACC{slash}PE7)") (class "Default")
      (node (ref "R26") (pin "2") (pinfunction "2_2") (pintype "passive"))
      (node (ref "Ub1") (pin "36") (pinfunction "~{XCLKS}/NOACC/PE7_36") (pintype "bidirectional"))
    )
    (net (code "103") (name "Net-(Ub1-~{XIRQ}{slash}PE0)") (class "Default")
      (node (ref "R22") (pin "2") (pinfunction "2_2") (pintype "passive"))
      (node (ref "Ub1") (pin "56") (pinfunction "~{XIRQ}/PE0_56") (pintype "input"))
    )
    (net (code "104") (name "Net-(Yb1-out)") (class "Default")
      (node (ref "R33") (pin "1") (pinfunction "1_1") (pintype "passive"))
      (node (ref "Yb1") (pin "3") (pinfunction "out_3") (pintype "passive"))
    )
    (net (code "105") (name "V+5A") (class "Default")
      (node (ref "C1") (pin "1") (pinfunction "1_1") (pintype "passive"))
      (node (ref "C15") (pin "1") (pinfunction "1_1") (pintype "passive"))
      (node (ref "C31") (pin "1") (pinfunction "1_1") (pintype "passive"))
      (node (ref "C32") (pin "2") (pinfunction "2_2") (pintype "passive"))
      (node (ref "C5") (pin "1") (pinfunction "1_1") (pintype "passive"))
      (node (ref "R39") (pin "1") (pinfunction "1_1") (pintype "passive"))
      (node (ref "U2") (pin "8") (pinfunction "VCC_8") (pintype "power_in"))
      (node (ref "U3") (pin "8") (pinfunction "VCC_8") (pintype "power_in"))
      (node (ref "Ub1") (pin "83") (pinfunction "VDDA_83") (pintype "power_in"))
      (node (ref "Ub1") (pin "84") (pinfunction "VRH_84") (pintype "input"))
    )
    (net (code "106") (name "V+5D") (class "Default")
      (node (ref "C16") (pin "1") (pinfunction "1_1") (pintype "passive"))
      (node (ref "C17") (pin "1") (pinfunction "1_1") (pintype "passive"))
      (node (ref "C26") (pin "1") (pinfunction "1_1") (pintype "passive"))
      (node (ref "C29") (pin "1") (pinfunction "1_1") (pintype "passive"))
      (node (ref "C30") (pin "2") (pinfunction "2_2") (pintype "passive"))
      (node (ref "Cb6") (pin "1") (pinfunction "1_1") (pintype "passive"))
      (node (ref "J10") (pin "1") (pinfunction "1_1") (pintype "passive"))
      (node (ref "J8") (pin "3") (pinfunction "3_3") (pintype "passive"))
      (node (ref "J9") (pin "2") (pinfunction "2_2") (pintype "passive"))
      (node (ref "JP11") (pin "6") (pinfunction "6_6") (pintype "passive"))
      (node (ref "R20") (pin "1") (pinfunction "1_1") (pintype "passive"))
      (node (ref "R21") (pin "1") (pinfunction "1_1") (pintype "passive"))
      (node (ref "R22") (pin "1") (pinfunction "1_1") (pintype "passive"))
      (node (ref "R23") (pin "1") (pinfunction "1_1") (pintype "passive"))
      (node (ref "R31") (pin "2") (pinfunction "2_2") (pintype "passive"))
      (node (ref "R35") (pin "2") (pinfunction "2_2") (pintype "passive"))
      (node (ref "R36") (pin "2") (pinfunction "2_2") (pintype "passive"))
      (node (ref "R38") (pin "2") (pinfunction "2_2") (pintype "passive"))
      (node (ref "R39") (pin "2") (pinfunction "2_2") (pintype "passive"))
      (node (ref "RP1") (pin "5") (pinfunction "5_5") (pintype "passive"))
      (node (ref "RP1") (pin "6") (pinfunction "6_6") (pintype "passive"))
      (node (ref "RP1") (pin "7") (pinfunction "7_7") (pintype "passive"))
      (node (ref "RP1") (pin "8") (pinfunction "8_8") (pintype "passive"))
      (node (ref "Ub1") (pin "107") (pinfunction "VDDX_107") (pintype "power_in"))
      (node (ref "Ub1") (pin "41") (pinfunction "VDDR_41") (pintype "power_in"))
      (node (ref "Yb1") (pin "4") (pinfunction "+_4") (pintype "passive"))
    )
    (net (code "107") (name "unconnected-(JP11-Pad3)") (class "Default")
      (node (ref "JP11") (pin "3") (pinfunction "3_3") (pintype "passive+no_connect"))
    )
    (net (code "108") (name "unconnected-(JP11-Pad5)") (class "Default")
      (node (ref "JP11") (pin "5") (pinfunction "5_5") (pintype "passive+no_connect"))
    )
    (net (code "109") (name "unconnected-(U2-BACK_PORCH-Pad5)") (class "Default")
      (node (ref "U2") (pin "5") (pinfunction "BACK_PORCH_5") (pintype "output"))
    )
    (net (code "110") (name "unconnected-(U3-BACK_PORCH-Pad5)") (class "Default")
      (node (ref "U3") (pin "5") (pinfunction "BACK_PORCH_5") (pintype "output"))
    )
    (net (code "111") (name "unconnected-(Ub1-ECLK{slash}PE4-Pad39)") (class "Default")
      (node (ref "Ub1") (pin "39") (pinfunction "ECLK/PE4_39") (pintype "bidirectional"))
    )
    (net (code "112") (name "unconnected-(Ub1-PJ6{slash}KWJ6{slash}RXCAN4{slash}SDA-Pad99)") (class "Default")
      (node (ref "Ub1") (pin "99") (pinfunction "PJ6/KWJ6/RXCAN4/SDA_99") (pintype "bidirectional"))
    )
    (net (code "113") (name "unconnected-(Ub1-PJ7{slash}KWJ7{slash}TXCAN4{slash}SCL-Pad98)") (class "Default")
      (node (ref "Ub1") (pin "98") (pinfunction "PJ7/KWJ7/TXCAN4/SCL_98") (pintype "bidirectional"))
    )
    (net (code "114") (name "unconnected-(Ub1-PWM7{slash}KWP7{slash}PP7-Pad109)") (class "Default")
      (node (ref "Ub1") (pin "109") (pinfunction "PWM7/KWP7/PP7_109") (pintype "bidirectional"))
    )
    (net (code "115") (name "unconnected-(Ub1-R{slash}~{W}{slash}PE2-Pad54)") (class "Default")
      (node (ref "Ub1") (pin "54") (pinfunction "R/~{W}/PE2_54") (pintype "bidirectional"))
    )
    (net (code "116") (name "unconnected-(Ub1-VSSPLL-Pad45)") (class "Default")
      (node (ref "Ub1") (pin "45") (pinfunction "VSSPLL_45") (pintype "power_in"))
    )
    (net (code "117") (name "unconnected-(Ub1-XADDR18{slash}PK4-Pad20)") (class "Default")
      (node (ref "Ub1") (pin "20") (pinfunction "XADDR18/PK4_20") (pintype "bidirectional"))
    )
    (net (code "118") (name "unconnected-(Ub1-XADDR19{slash}PK5-Pad19)") (class "Default")
      (node (ref "Ub1") (pin "19") (pinfunction "XADDR19/PK5_19") (pintype "bidirectional"))
    )
    (net (code "119") (name "unconnected-(Ub1-~{ECS}{slash}ROMCTL{slash}PK7-Pad108)") (class "Default")
      (node (ref "Ub1") (pin "108") (pinfunction "~{ECS}/ROMCTL/PK7_108") (pintype "bidirectional"))
    )
    (net (code "120") (name "unconnected-(Ub1-~{LSTRB}{slash}~{TAGLO}{slash}PE3-Pad53)") (class "Default")
      (node (ref "Ub1") (pin "53") (pinfunction "~{LSTRB}/~{TAGLO}/PE3_53") (pintype "bidirectional"))
    )
    (net (code "121") (name "unconnected-(Yb1-nc-Pad1)") (class "Default")
      (node (ref "Yb1") (pin "1") (pinfunction "nc_1") (pintype "passive+no_connect"))
    )
  )
)
